# ASD2611.net
KiCad netlist of a schematic drawn in EAGLE
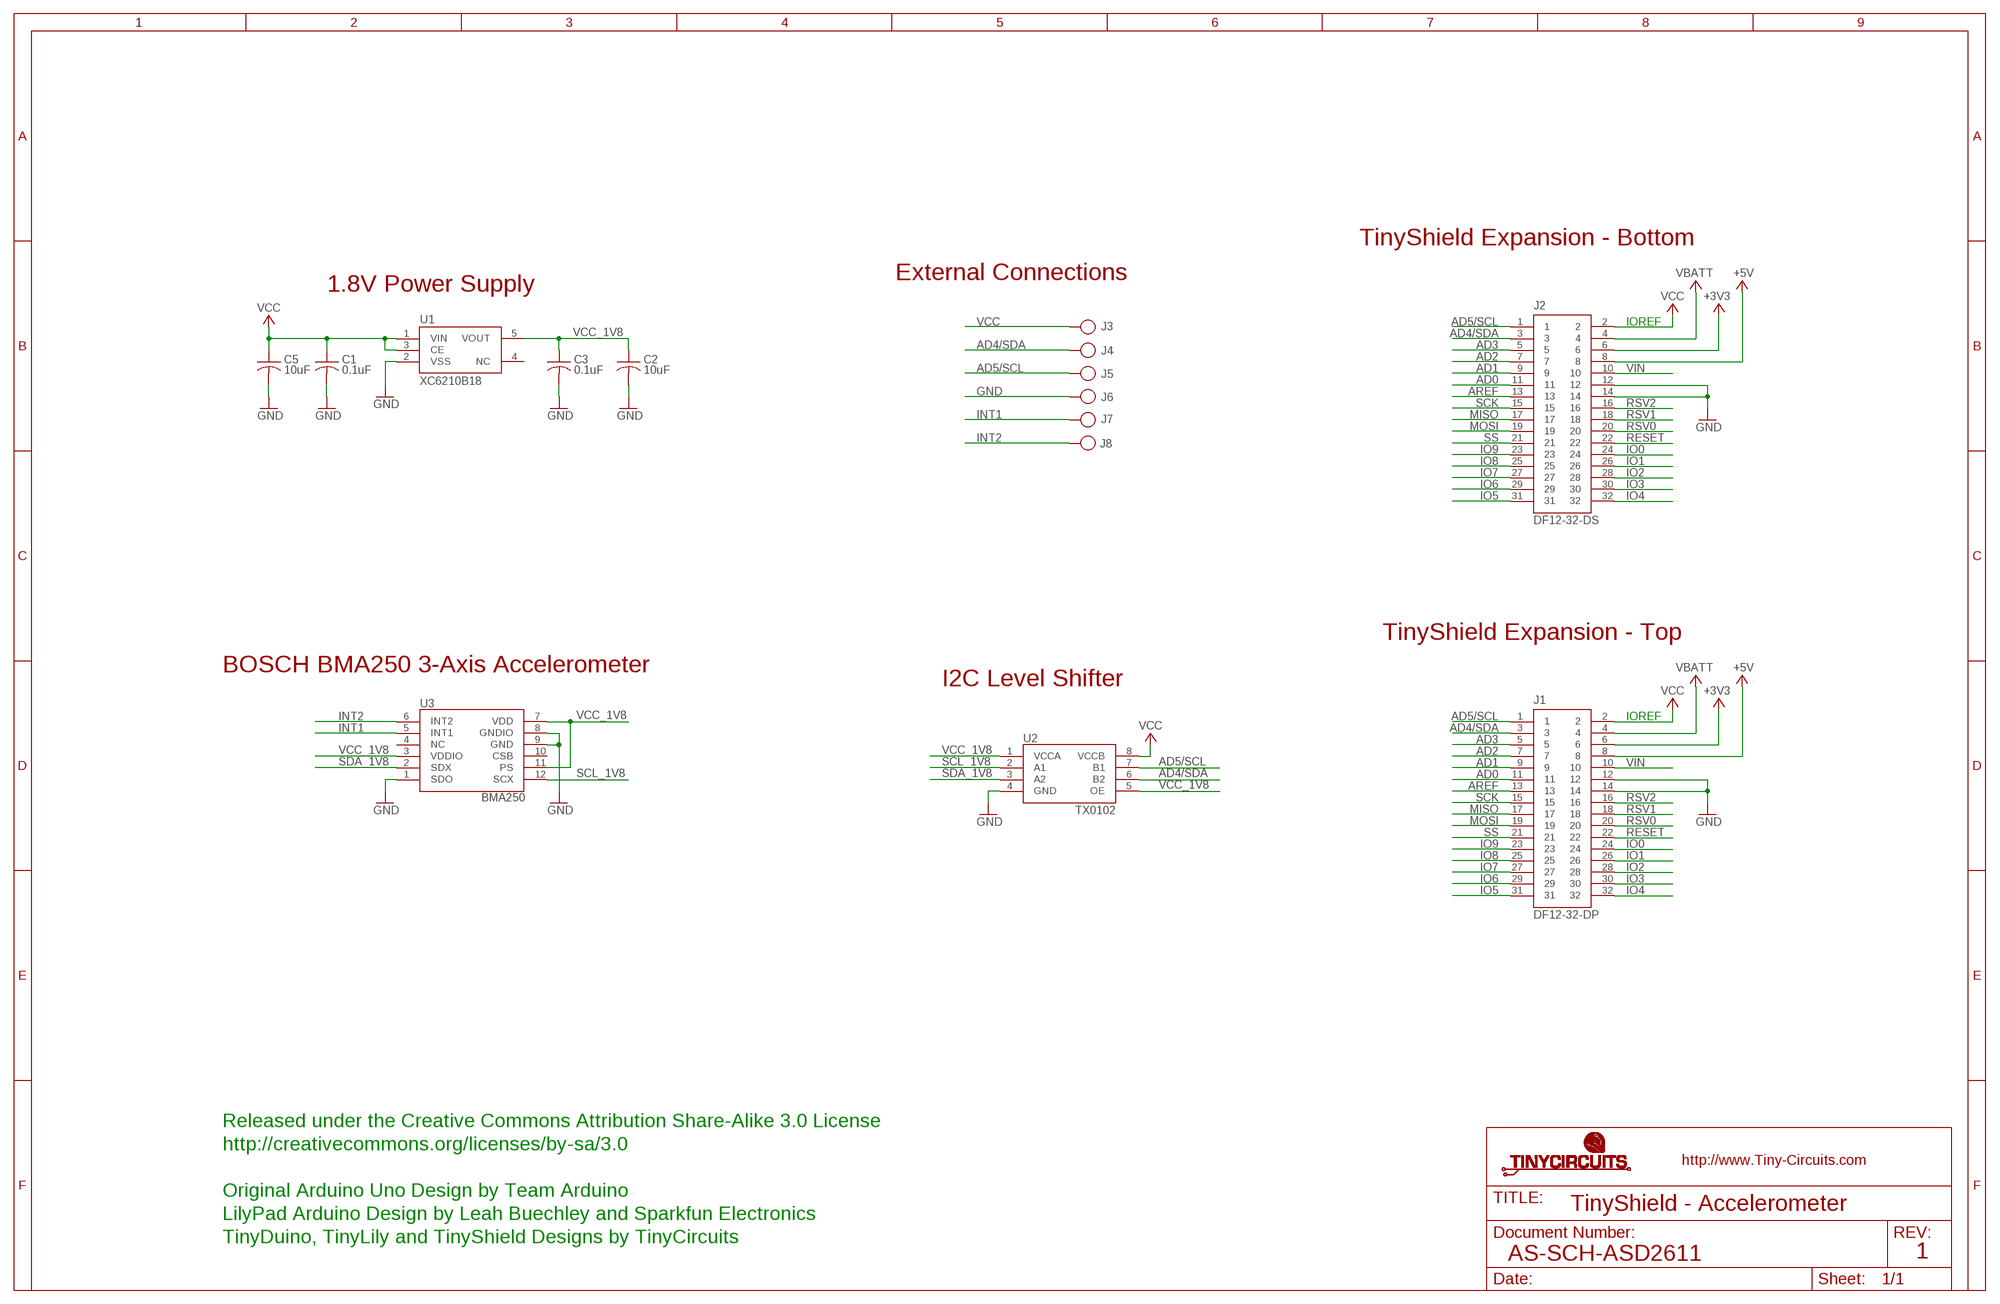
[diagram p0: schematic, sheet 1]

(export (version "E")
  (design (tool "Eeschema 10.0.6"))
  (components
    (comp (ref "C1")
      (value "0.1uF")
      (footprint "eagle-import:C0402")
      (fields (field (name "PARTNO") "AS-ITM-00008") (field (name "PARTNO_1") "AS-ITM-00008"))
      (libsource (lib "eagle-import") (part "AS-ITM-00008"))
    )
    (comp (ref "C2")
      (value "10uF")
      (footprint "eagle-import:C0805")
      (fields (field (name "PARTNO") "AS-ITM-00045") (field (name "PARTNO_1") "AS-ITM-00045"))
      (libsource (lib "eagle-import") (part "AS-ITM-00045"))
    )
    (comp (ref "C3")
      (value "0.1uF")
      (footprint "eagle-import:C0402")
      (fields (field (name "PARTNO") "AS-ITM-00008") (field (name "PARTNO_1") "AS-ITM-00008"))
      (libsource (lib "eagle-import") (part "AS-ITM-00008"))
    )
    (comp (ref "C5")
      (value "10uF")
      (footprint "eagle-import:C0805")
      (fields (field (name "PARTNO") "AS-ITM-00045"))
      (libsource (lib "eagle-import") (part "AS-ITM-00045"))
    )
    (comp (ref "J1")
      (value "DF12-32-DP")
      (footprint "eagle-import:DF12-32-DP")
      (fields (field (name "PARTNO") "AS-ITM-00015") (field (name "PARTNO_1") "AS-ITM-00015"))
      (libsource (lib "eagle-import") (part "AS-ITM-00015"))
    )
    (comp (ref "J2")
      (value "DF12-32-DS")
      (footprint "eagle-import:DF12-32-DS")
      (fields (field (name "PARTNO") "AS-ITM-00012") (field (name "PARTNO_1") "AS-ITM-00012"))
      (libsource (lib "eagle-import") (part "AS-ITM-00012"))
    )
    (comp (ref "J3")
      (value "PIN_1X.1\"")
      (footprint "eagle-import:1X.1_")
      (libsource (lib "eagle-import") (part "PIN_1X.1{dblquote}"))
    )
    (comp (ref "J4")
      (value "PIN_1X.1\"")
      (footprint "eagle-import:1X.1_")
      (libsource (lib "eagle-import") (part "PIN_1X.1{dblquote}"))
    )
    (comp (ref "J5")
      (value "PIN_1X.1\"")
      (footprint "eagle-import:1X.1_")
      (libsource (lib "eagle-import") (part "PIN_1X.1{dblquote}"))
    )
    (comp (ref "J6")
      (value "PIN_1X.1\"")
      (footprint "eagle-import:1X.1_")
      (libsource (lib "eagle-import") (part "PIN_1X.1{dblquote}"))
    )
    (comp (ref "J7")
      (value "PIN_1X.1\"")
      (footprint "eagle-import:1X.1_")
      (libsource (lib "eagle-import") (part "PIN_1X.1{dblquote}"))
    )
    (comp (ref "J8")
      (value "PIN_1X.1\"")
      (footprint "eagle-import:1X.1_")
      (libsource (lib "eagle-import") (part "PIN_1X.1{dblquote}"))
    )
    (comp (ref "U1")
      (value "XC6210B18")
      (footprint "eagle-import:SOT-25")
      (fields (field (name "PARTNO") "AS-ITM-00075") (field (name "PARTNO_1") "AS-ITM-00075"))
      (libsource (lib "eagle-import") (part "AS-ITM-00075"))
    )
    (comp (ref "U2")
      (value "TX0102")
      (footprint "eagle-import:DQE(R-PX2SON-N8)")
      (fields (field (name "PARTNO") "AS-ITM-00073"))
      (libsource (lib "eagle-import") (part "AS-ITM-00073"))
    )
    (comp (ref "U3")
      (value "BMA250")
      (footprint "eagle-import:3-AXIS_ACCELEROMETER")
      (fields (field (name "PARTNO") "AS-ITM-00070"))
      (libsource (lib "eagle-import") (part "AS-ITM-00070"))
    )
  )
  (nets
    (net (code "1") (name "+3V3") (class "Default")
      (node (ref "J1") (pin "6") (pinfunction "6_6") (pintype "bidirectional"))
      (node (ref "J2") (pin "6") (pinfunction "6_6") (pintype "bidirectional"))
    )
    (net (code "2") (name "+5V") (class "Default")
      (node (ref "J1") (pin "8") (pinfunction "8_8") (pintype "bidirectional"))
      (node (ref "J2") (pin "8") (pinfunction "8_8") (pintype "bidirectional"))
    )
    (net (code "3") (name "/AD0") (class "Default")
      (node (ref "J1") (pin "11") (pinfunction "11_11") (pintype "bidirectional"))
      (node (ref "J2") (pin "11") (pinfunction "11_11") (pintype "bidirectional"))
    )
    (net (code "4") (name "/AD1") (class "Default")
      (node (ref "J1") (pin "9") (pinfunction "9_9") (pintype "bidirectional"))
      (node (ref "J2") (pin "9") (pinfunction "9_9") (pintype "bidirectional"))
    )
    (net (code "5") (name "/AD2") (class "Default")
      (node (ref "J1") (pin "7") (pinfunction "7_7") (pintype "bidirectional"))
      (node (ref "J2") (pin "7") (pinfunction "7_7") (pintype "bidirectional"))
    )
    (net (code "6") (name "/AD3") (class "Default")
      (node (ref "J1") (pin "5") (pinfunction "5_5") (pintype "bidirectional"))
      (node (ref "J2") (pin "5") (pinfunction "5_5") (pintype "bidirectional"))
    )
    (net (code "7") (name "/AD4{slash}SDA") (class "Default")
      (node (ref "J1") (pin "3") (pinfunction "3_3") (pintype "bidirectional"))
      (node (ref "J2") (pin "3") (pinfunction "3_3") (pintype "bidirectional"))
      (node (ref "J4") (pin "1") (pinfunction "1_1") (pintype "bidirectional"))
      (node (ref "U2") (pin "6") (pinfunction "B2_6") (pintype "bidirectional"))
    )
    (net (code "8") (name "/AD5{slash}SCL") (class "Default")
      (node (ref "J1") (pin "1") (pinfunction "1_1") (pintype "bidirectional"))
      (node (ref "J2") (pin "1") (pinfunction "1_1") (pintype "bidirectional"))
      (node (ref "J5") (pin "1") (pinfunction "1_1") (pintype "bidirectional"))
      (node (ref "U2") (pin "7") (pinfunction "B1_7") (pintype "bidirectional"))
    )
    (net (code "9") (name "/AREF") (class "Default")
      (node (ref "J1") (pin "13") (pinfunction "13_13") (pintype "bidirectional"))
      (node (ref "J2") (pin "13") (pinfunction "13_13") (pintype "bidirectional"))
    )
    (net (code "10") (name "/INT1") (class "Default")
      (node (ref "J7") (pin "1") (pinfunction "1_1") (pintype "bidirectional"))
      (node (ref "U3") (pin "5") (pinfunction "INT1_5") (pintype "bidirectional"))
    )
    (net (code "11") (name "/INT2") (class "Default")
      (node (ref "J8") (pin "1") (pinfunction "1_1") (pintype "bidirectional"))
      (node (ref "U3") (pin "6") (pinfunction "INT2_6") (pintype "bidirectional"))
    )
    (net (code "12") (name "/IO0") (class "Default")
      (node (ref "J1") (pin "24") (pinfunction "24_24") (pintype "bidirectional"))
      (node (ref "J2") (pin "24") (pinfunction "24_24") (pintype "bidirectional"))
    )
    (net (code "13") (name "/IO1") (class "Default")
      (node (ref "J1") (pin "26") (pinfunction "26_26") (pintype "bidirectional"))
      (node (ref "J2") (pin "26") (pinfunction "26_26") (pintype "bidirectional"))
    )
    (net (code "14") (name "/IO2") (class "Default")
      (node (ref "J1") (pin "28") (pinfunction "28_28") (pintype "bidirectional"))
      (node (ref "J2") (pin "28") (pinfunction "28_28") (pintype "bidirectional"))
    )
    (net (code "15") (name "/IO3") (class "Default")
      (node (ref "J1") (pin "30") (pinfunction "30_30") (pintype "bidirectional"))
      (node (ref "J2") (pin "30") (pinfunction "30_30") (pintype "bidirectional"))
    )
    (net (code "16") (name "/IO4") (class "Default")
      (node (ref "J1") (pin "32") (pinfunction "32_32") (pintype "bidirectional"))
      (node (ref "J2") (pin "32") (pinfunction "32_32") (pintype "bidirectional"))
    )
    (net (code "17") (name "/IO5") (class "Default")
      (node (ref "J1") (pin "31") (pinfunction "31_31") (pintype "bidirectional"))
      (node (ref "J2") (pin "31") (pinfunction "31_31") (pintype "bidirectional"))
    )
    (net (code "18") (name "/IO6") (class "Default")
      (node (ref "J1") (pin "29") (pinfunction "29_29") (pintype "bidirectional"))
      (node (ref "J2") (pin "29") (pinfunction "29_29") (pintype "bidirectional"))
    )
    (net (code "19") (name "/IO7") (class "Default")
      (node (ref "J1") (pin "27") (pinfunction "27_27") (pintype "bidirectional"))
      (node (ref "J2") (pin "27") (pinfunction "27_27") (pintype "bidirectional"))
    )
    (net (code "20") (name "/IO8") (class "Default")
      (node (ref "J1") (pin "25") (pinfunction "25_25") (pintype "bidirectional"))
      (node (ref "J2") (pin "25") (pinfunction "25_25") (pintype "bidirectional"))
    )
    (net (code "21") (name "/IO9") (class "Default")
      (node (ref "J1") (pin "23") (pinfunction "23_23") (pintype "bidirectional"))
      (node (ref "J2") (pin "23") (pinfunction "23_23") (pintype "bidirectional"))
    )
    (net (code "22") (name "/MISO") (class "Default")
      (node (ref "J1") (pin "17") (pinfunction "17_17") (pintype "bidirectional"))
      (node (ref "J2") (pin "17") (pinfunction "17_17") (pintype "bidirectional"))
    )
    (net (code "23") (name "/MOSI") (class "Default")
      (node (ref "J1") (pin "19") (pinfunction "19_19") (pintype "bidirectional"))
      (node (ref "J2") (pin "19") (pinfunction "19_19") (pintype "bidirectional"))
    )
    (net (code "24") (name "/RESET") (class "Default")
      (node (ref "J1") (pin "22") (pinfunction "22_22") (pintype "bidirectional"))
      (node (ref "J2") (pin "22") (pinfunction "22_22") (pintype "bidirectional"))
    )
    (net (code "25") (name "/RSV0") (class "Default")
      (node (ref "J1") (pin "20") (pinfunction "20_20") (pintype "bidirectional"))
      (node (ref "J2") (pin "20") (pinfunction "20_20") (pintype "bidirectional"))
    )
    (net (code "26") (name "/RSV1") (class "Default")
      (node (ref "J1") (pin "18") (pinfunction "18_18") (pintype "bidirectional"))
      (node (ref "J2") (pin "18") (pinfunction "18_18") (pintype "bidirectional"))
    )
    (net (code "27") (name "/RSV2") (class "Default")
      (node (ref "J1") (pin "16") (pinfunction "16_16") (pintype "bidirectional"))
      (node (ref "J2") (pin "16") (pinfunction "16_16") (pintype "bidirectional"))
    )
    (net (code "28") (name "/SCK") (class "Default")
      (node (ref "J1") (pin "15") (pinfunction "15_15") (pintype "bidirectional"))
      (node (ref "J2") (pin "15") (pinfunction "15_15") (pintype "bidirectional"))
    )
    (net (code "29") (name "/SCL_1V8") (class "Default")
      (node (ref "U2") (pin "2") (pinfunction "A1_2") (pintype "bidirectional"))
      (node (ref "U3") (pin "12") (pinfunction "SCX_12") (pintype "bidirectional"))
    )
    (net (code "30") (name "/SDA_1V8") (class "Default")
      (node (ref "U2") (pin "3") (pinfunction "A2_3") (pintype "bidirectional"))
      (node (ref "U3") (pin "2") (pinfunction "SDX_2") (pintype "bidirectional"))
    )
    (net (code "31") (name "/SS") (class "Default")
      (node (ref "J1") (pin "21") (pinfunction "21_21") (pintype "bidirectional"))
      (node (ref "J2") (pin "21") (pinfunction "21_21") (pintype "bidirectional"))
    )
    (net (code "32") (name "/VCC_1V8") (class "Default")
      (node (ref "C2") (pin "1") (pinfunction "1_1") (pintype "passive"))
      (node (ref "C3") (pin "1") (pinfunction "1_1") (pintype "passive"))
      (node (ref "U1") (pin "5") (pinfunction "VOUT_5") (pintype "bidirectional"))
      (node (ref "U2") (pin "1") (pinfunction "VCCA_1") (pintype "bidirectional"))
      (node (ref "U2") (pin "5") (pinfunction "OE_5") (pintype "bidirectional"))
      (node (ref "U3") (pin "11") (pinfunction "PS_11") (pintype "bidirectional"))
      (node (ref "U3") (pin "3") (pinfunction "VDDIO_3") (pintype "bidirectional"))
      (node (ref "U3") (pin "7") (pinfunction "VDD_7") (pintype "bidirectional"))
    )
    (net (code "33") (name "/VIN") (class "Default")
      (node (ref "J1") (pin "10") (pinfunction "10_10") (pintype "bidirectional"))
      (node (ref "J2") (pin "10") (pinfunction "10_10") (pintype "bidirectional"))
    )
    (net (code "34") (name "GND") (class "Default")
      (node (ref "C1") (pin "2") (pinfunction "2_2") (pintype "passive"))
      (node (ref "C2") (pin "2") (pinfunction "2_2") (pintype "passive"))
      (node (ref "C3") (pin "2") (pinfunction "2_2") (pintype "passive"))
      (node (ref "C5") (pin "2") (pinfunction "2_2") (pintype "passive"))
      (node (ref "J1") (pin "12") (pinfunction "12_12") (pintype "bidirectional"))
      (node (ref "J1") (pin "14") (pinfunction "14_14") (pintype "bidirectional"))
      (node (ref "J2") (pin "12") (pinfunction "12_12") (pintype "bidirectional"))
      (node (ref "J2") (pin "14") (pinfunction "14_14") (pintype "bidirectional"))
      (node (ref "J6") (pin "1") (pinfunction "1_1") (pintype "bidirectional"))
      (node (ref "U1") (pin "2") (pinfunction "VSS_2") (pintype "power_in"))
      (node (ref "U2") (pin "4") (pinfunction "GND_4") (pintype "bidirectional"))
      (node (ref "U3") (pin "1") (pinfunction "SDO_1") (pintype "bidirectional"))
      (node (ref "U3") (pin "8") (pinfunction "GNDIO_8") (pintype "bidirectional"))
      (node (ref "U3") (pin "9") (pinfunction "GND_9") (pintype "bidirectional"))
    )
    (net (code "35") (name "VBATT") (class "Default")
      (node (ref "J1") (pin "4") (pinfunction "4_4") (pintype "bidirectional"))
      (node (ref "J2") (pin "4") (pinfunction "4_4") (pintype "bidirectional"))
    )
    (net (code "36") (name "VCC") (class "Default")
      (node (ref "C1") (pin "1") (pinfunction "1_1") (pintype "passive"))
      (node (ref "C5") (pin "1") (pinfunction "1_1") (pintype "passive"))
      (node (ref "J1") (pin "2") (pinfunction "2_2") (pintype "bidirectional"))
      (node (ref "J2") (pin "2") (pinfunction "2_2") (pintype "bidirectional"))
      (node (ref "J3") (pin "1") (pinfunction "1_1") (pintype "bidirectional"))
      (node (ref "U1") (pin "1") (pinfunction "VIN_1") (pintype "bidirectional"))
      (node (ref "U1") (pin "3") (pinfunction "CE_3") (pintype "bidirectional"))
      (node (ref "U2") (pin "8") (pinfunction "VCCB_8") (pintype "bidirectional"))
    )
    (net (code "37") (name "unconnected-(U1-NC-Pad4)") (class "Default")
      (node (ref "U1") (pin "4") (pinfunction "NC_4") (pintype "bidirectional"))
    )
    (net (code "38") (name "unconnected-(U3-CSB-Pad10)") (class "Default")
      (node (ref "U3") (pin "10") (pinfunction "CSB_10") (pintype "bidirectional"))
    )
    (net (code "39") (name "unconnected-(U3-NC-Pad4)") (class "Default")
      (node (ref "U3") (pin "4") (pinfunction "NC_4") (pintype "bidirectional"))
    )
  )
)
